# Main.net
KiCad netlist of a schematic drawn in Altium Designer
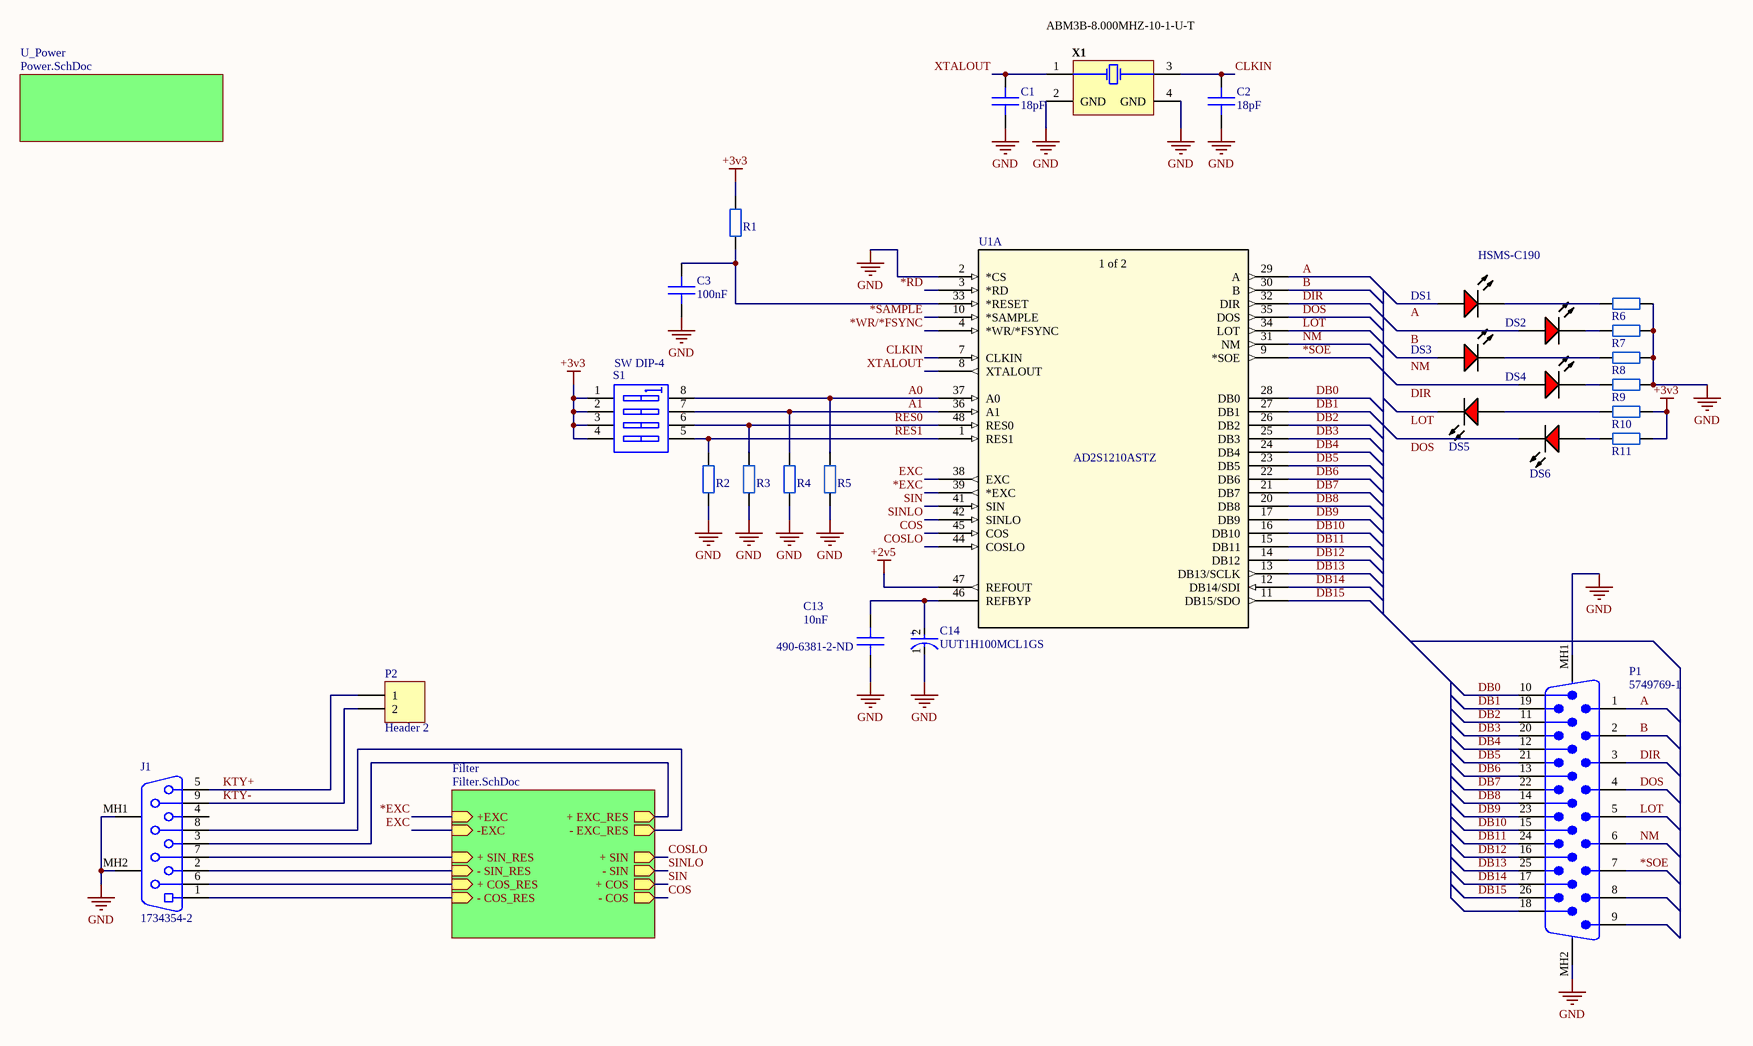
[diagram p0: Main.SchDoc]

(export (version "E")
  (design (tool "Eeschema 10.0.6"))
  (components
    (comp (ref "C1")
      (value "18pF")
      (footprint "C0603 (1608)")
      (fields (field (name "Comment") "Cap SMD"))
      (libsource (lib "Moto Symbol Lib") (part "Cap SMD"))
    )
    (comp (ref "C2")
      (value "18pF")
      (footprint "C0603 (1608)")
      (fields (field (name "Comment") "Cap SMD"))
      (libsource (lib "Moto Symbol Lib") (part "Cap SMD"))
    )
    (comp (ref "C3")
      (value "100nF")
      (footprint "C0603 (1608)")
      (fields (field (name "Comment") "Cap SMD"))
      (libsource (lib "Moto Symbol Lib") (part "Cap SMD"))
    )
    (comp (ref "C13")
      (value "10nF")
      (footprint "C0603 (1608)")
      (description "Multilayer Ceramic Capacitors MLCC - SMD/SMT 2200pF 50Volts 2%")
      (fields
        (field (name "SUPPLIER PART NUMBER 1") "490-6381-2-ND")
        (field (name "MANUFACTURER") "Murata")
        (field (name "MANUFACTURER PART NUMBER") "GRM1885C1H222GA01D")
      )
      (libsource (lib "Moto Symbol Lib") (part "Cap SMD"))
    )
    (comp (ref "C14")
      (value "UUT1H100MCL1GS")
      (footprint "FP-UUT1H100MCL1GS-MFG")
      (description "CAP ALUM 10UF 20% 50V SMD")
      (fields (field (name "VOLTAGE") "50V") (field (name "TOLERANCE") "20%"))
      (libsource (lib "Altium Content Vault") (part "cf48714ba7e38822c1575c7ec0b6d1f"))
    )
    (comp (ref "DS1")
      (value "HSMS-C190")
      (footprint "AVAG-HSMX-C190_V")
      (description "LED Uni-Color Red, 52 mW, 20 mA, -40 to 85 degC, 2-Pin SMD, RoHS, Tape and Reel")
      (fields (field (name "MANUFACTURER") "Avago"))
      (libsource (lib "Altium Content Vault") (part "LED-RED-AK-2"))
    )
    (comp (ref "DS2")
      (value "HSMS-C190")
      (footprint "AVAG-HSMX-C190_V")
      (description "LED Uni-Color Red, 52 mW, 20 mA, -40 to 85 degC, 2-Pin SMD, RoHS, Tape and Reel")
      (fields (field (name "MANUFACTURER") "Avago"))
      (libsource (lib "Altium Content Vault") (part "LED-RED-AK-2"))
    )
    (comp (ref "DS3")
      (value "HSMS-C190")
      (footprint "AVAG-HSMX-C190_V")
      (description "LED Uni-Color Red, 52 mW, 20 mA, -40 to 85 degC, 2-Pin SMD, RoHS, Tape and Reel")
      (fields (field (name "MANUFACTURER") "Avago"))
      (libsource (lib "Altium Content Vault") (part "LED-RED-AK-2"))
    )
    (comp (ref "DS4")
      (value "HSMS-C190")
      (footprint "AVAG-HSMX-C190_V")
      (description "LED Uni-Color Red, 52 mW, 20 mA, -40 to 85 degC, 2-Pin SMD, RoHS, Tape and Reel")
      (fields (field (name "MANUFACTURER") "Avago"))
      (libsource (lib "Altium Content Vault") (part "LED-RED-AK-2"))
    )
    (comp (ref "DS5")
      (value "HSMS-C190")
      (footprint "AVAG-HSMX-C190_V")
      (description "LED Uni-Color Red, 52 mW, 20 mA, -40 to 85 degC, 2-Pin SMD, RoHS, Tape and Reel")
      (fields (field (name "MANUFACTURER") "Avago"))
      (libsource (lib "Altium Content Vault") (part "LED-RED-AK-2"))
    )
    (comp (ref "DS6")
      (value "HSMS-C190")
      (footprint "AVAG-HSMX-C190_V")
      (description "LED Uni-Color Red, 52 mW, 20 mA, -40 to 85 degC, 2-Pin SMD, RoHS, Tape and Reel")
      (fields (field (name "MANUFACTURER") "Avago"))
      (libsource (lib "Altium Content Vault") (part "LED-RED-AK-2"))
    )
    (comp (ref "J1")
      (value "1734354-2")
      (footprint "TECO-1734354-2_V")
      (fields (field (name "MANUFACTURER") "TE Connectivity"))
      (libsource (lib "Altium Content Vault") (part "CN-2S-2F-D9"))
    )
    (comp (ref "P1")
      (value "5749769-1")
      (footprint "TECO-5749769-1_V")
      (fields (field (name "MANUFACTURER") "TEConnectivity"))
      (libsource (lib "Altium Content Vault") (part "CN-3S-2M-D26"))
    )
    (comp (ref "P2")
      (value "Header 2")
      (footprint "HDR1X2")
      (description "Header, 2-Pin")
      (fields (field (name "PUBLISHER") "Altium Limited"))
      (libsource (lib "Miscellaneous Connectors") (part "Header 2"))
    )
    (comp (ref "R1")
      (value "Res")
      (footprint "R0603 (1608)")
      (libsource (lib "Moto Symbol Lib") (part "Resistor EU"))
    )
    (comp (ref "R2")
      (value "Res")
      (footprint "R0603 (1608)")
      (libsource (lib "Moto Symbol Lib") (part "Resistor EU"))
    )
    (comp (ref "R3")
      (value "Res")
      (footprint "R0603 (1608)")
      (libsource (lib "Moto Symbol Lib") (part "Resistor EU"))
    )
    (comp (ref "R4")
      (value "Res")
      (footprint "R0603 (1608)")
      (libsource (lib "Moto Symbol Lib") (part "Resistor EU"))
    )
    (comp (ref "R5")
      (value "Res")
      (footprint "R0603 (1608)")
      (libsource (lib "Moto Symbol Lib") (part "Resistor EU"))
    )
    (comp (ref "R6")
      (value "1K")
      (footprint "R0603 (1608)")
      (libsource (lib "Moto Symbol Lib") (part "Resistor EU"))
    )
    (comp (ref "R7")
      (value "1K")
      (footprint "R0603 (1608)")
      (libsource (lib "Moto Symbol Lib") (part "Resistor EU"))
    )
    (comp (ref "R8")
      (value "1K")
      (footprint "R0603 (1608)")
      (libsource (lib "Moto Symbol Lib") (part "Resistor EU"))
    )
    (comp (ref "R9")
      (value "1K")
      (footprint "R0603 (1608)")
      (libsource (lib "Moto Symbol Lib") (part "Resistor EU"))
    )
    (comp (ref "R10")
      (value "1K")
      (footprint "R0603 (1608)")
      (libsource (lib "Moto Symbol Lib") (part "Resistor EU"))
    )
    (comp (ref "R11")
      (value "1K")
      (footprint "R0603 (1608)")
      (libsource (lib "Moto Symbol Lib") (part "Resistor EU"))
    )
    (comp (ref "S1")
      (value "SW DIP-4")
      (footprint "SO8_M")
      (description "DIP Switch, 4 Position, SPST")
      (fields (field (name "PUBLISHER") "Altium Limited"))
      (libsource (lib "Miscellaneous Devices") (part "SW DIP-4"))
    )
    (comp (ref "U1")
      (value "AD2S1210ASTZ")
      (footprint "ST_48_ADI")
      (description "No Description Available")
      (fields (field (name "COPYRIGHT") "Copyright (C) 2018 Accelerated Designs. All rights reserved"))
      (libsource (lib "Resolver Lib") (part "AD2S1210ASTZ"))
    )
    (comp (ref "X1")
      (value "ABM3B-8.000MHZ-10-1-U-T")
      (footprint "ABRA-ABM3B_V")
      (description "Ceramic Crystal, 8 MHz, +/- 10 ppm, -10 to 60 degC, 4-Pin SMD, RoHS, Tape and Reel")
      (fields (field (name "MANUFACTURER") "Abracon-LLC"))
      (libsource (lib "Altium Content Vault") (part "XTAL-1-3-4"))
    )
  )
  (nets
    (net (code "1") (name "+2v5") (class "Default")
      (node (ref "U1") (pin "47") (pinfunction "REFOUT_47") (pintype "output"))
    )
    (net (code "2") (name "+3v3") (class "Default")
      (node (ref "R1") (pin "2") (pinfunction "2_2") (pintype "power_in"))
      (node (ref "R10") (pin "2") (pinfunction "2_2") (pintype "power_in"))
      (node (ref "R11") (pin "2") (pinfunction "2_2") (pintype "power_in"))
      (node (ref "S1") (pin "1") (pinfunction "A1_1") (pintype "passive"))
      (node (ref "S1") (pin "2") (pinfunction "A2_2") (pintype "passive"))
      (node (ref "S1") (pin "3") (pinfunction "A3_3") (pintype "passive"))
      (node (ref "S1") (pin "4") (pinfunction "A4_4") (pintype "passive"))
    )
    (net (code "3") (name "/*EXC") (class "Default")
      (node (ref "U1") (pin "39") (pinfunction "*EXC_39") (pintype "output"))
    )
    (net (code "4") (name "/*RD") (class "Default")
      (node (ref "U1") (pin "3") (pinfunction "*RD_3") (pintype "input"))
    )
    (net (code "5") (name "/*SAMPLE") (class "Default")
      (node (ref "U1") (pin "10") (pinfunction "*SAMPLE_10") (pintype "input"))
    )
    (net (code "6") (name "/*SOE") (class "Default")
      (node (ref "P1") (pin "7") (pinfunction "7_7") (pintype "passive"))
      (node (ref "U1") (pin "9") (pinfunction "*SOE_9") (pintype "output"))
    )
    (net (code "7") (name "/*WR{slash}*FSYNC") (class "Default")
      (node (ref "U1") (pin "4") (pinfunction "*WR/*FSYNC_4") (pintype "input"))
    )
    (net (code "8") (name "/+ COS_RES") (class "Default")
      (node (ref "J1") (pin "6") (pinfunction "6_6") (pintype "passive"))
    )
    (net (code "9") (name "/+ EXC_RES") (class "Default")
      (node (ref "J1") (pin "3") (pinfunction "3_3") (pintype "passive"))
    )
    (net (code "10") (name "/+ SIN_RES") (class "Default")
      (node (ref "J1") (pin "7") (pinfunction "7_7") (pintype "passive"))
    )
    (net (code "11") (name "/- COS_RES") (class "Default")
      (node (ref "J1") (pin "1") (pinfunction "1_1") (pintype "passive"))
    )
    (net (code "12") (name "/- EXC_RES") (class "Default")
      (node (ref "J1") (pin "8") (pinfunction "8_8") (pintype "passive"))
    )
    (net (code "13") (name "/- SIN_RES") (class "Default")
      (node (ref "J1") (pin "2") (pinfunction "2_2") (pintype "passive"))
    )
    (net (code "14") (name "/A") (class "Default")
      (node (ref "DS1") (pin "1") (pinfunction "A_1") (pintype "passive"))
      (node (ref "P1") (pin "1") (pinfunction "1_1") (pintype "passive"))
      (node (ref "U1") (pin "29") (pinfunction "A_29") (pintype "output"))
    )
    (net (code "15") (name "/A0") (class "Default")
      (node (ref "R5") (pin "2") (pinfunction "2_2") (pintype "power_in"))
      (node (ref "S1") (pin "8") (pinfunction "B1_8") (pintype "passive"))
      (node (ref "U1") (pin "37") (pinfunction "A0_37") (pintype "input"))
    )
    (net (code "16") (name "/A1") (class "Default")
      (node (ref "R4") (pin "2") (pinfunction "2_2") (pintype "power_in"))
      (node (ref "S1") (pin "7") (pinfunction "B2_7") (pintype "passive"))
      (node (ref "U1") (pin "36") (pinfunction "A1_36") (pintype "input"))
    )
    (net (code "17") (name "/B") (class "Default")
      (node (ref "DS2") (pin "1") (pinfunction "A_1") (pintype "passive"))
      (node (ref "P1") (pin "2") (pinfunction "2_2") (pintype "passive"))
      (node (ref "U1") (pin "30") (pinfunction "B_30") (pintype "output"))
    )
    (net (code "18") (name "/CLKIN") (class "Default")
      (node (ref "C2") (pin "2") (pinfunction "2_2") (pintype "power_in"))
      (node (ref "U1") (pin "7") (pinfunction "CLKIN_7") (pintype "input"))
      (node (ref "X1") (pin "3") (pinfunction "X2_3") (pintype "passive"))
    )
    (net (code "19") (name "/COS") (class "Default")
      (node (ref "U1") (pin "45") (pinfunction "COS_45") (pintype "input"))
    )
    (net (code "20") (name "/COSLO") (class "Default")
      (node (ref "U1") (pin "44") (pinfunction "COSLO_44") (pintype "input"))
    )
    (net (code "21") (name "/DB0") (class "Default")
      (node (ref "P1") (pin "10") (pinfunction "10_10") (pintype "passive"))
      (node (ref "U1") (pin "28") (pinfunction "DB0_28") (pintype "passive"))
    )
    (net (code "22") (name "/DB1") (class "Default")
      (node (ref "P1") (pin "19") (pinfunction "19_19") (pintype "passive"))
      (node (ref "U1") (pin "27") (pinfunction "DB1_27") (pintype "passive"))
    )
    (net (code "23") (name "/DB2") (class "Default")
      (node (ref "P1") (pin "11") (pinfunction "11_11") (pintype "passive"))
      (node (ref "U1") (pin "26") (pinfunction "DB2_26") (pintype "passive"))
    )
    (net (code "24") (name "/DB3") (class "Default")
      (node (ref "P1") (pin "20") (pinfunction "20_20") (pintype "passive"))
      (node (ref "U1") (pin "25") (pinfunction "DB3_25") (pintype "passive"))
    )
    (net (code "25") (name "/DB4") (class "Default")
      (node (ref "P1") (pin "12") (pinfunction "12_12") (pintype "passive"))
      (node (ref "U1") (pin "24") (pinfunction "DB4_24") (pintype "passive"))
    )
    (net (code "26") (name "/DB5") (class "Default")
      (node (ref "P1") (pin "21") (pinfunction "21_21") (pintype "passive"))
      (node (ref "U1") (pin "23") (pinfunction "DB5_23") (pintype "passive"))
    )
    (net (code "27") (name "/DB6") (class "Default")
      (node (ref "P1") (pin "13") (pinfunction "13_13") (pintype "passive"))
      (node (ref "U1") (pin "22") (pinfunction "DB6_22") (pintype "passive"))
    )
    (net (code "28") (name "/DB7") (class "Default")
      (node (ref "P1") (pin "22") (pinfunction "22_22") (pintype "passive"))
      (node (ref "U1") (pin "21") (pinfunction "DB7_21") (pintype "passive"))
    )
    (net (code "29") (name "/DB8") (class "Default")
      (node (ref "P1") (pin "14") (pinfunction "14_14") (pintype "passive"))
      (node (ref "U1") (pin "20") (pinfunction "DB8_20") (pintype "passive"))
    )
    (net (code "30") (name "/DB9") (class "Default")
      (node (ref "P1") (pin "23") (pinfunction "23_23") (pintype "passive"))
      (node (ref "U1") (pin "17") (pinfunction "DB9_17") (pintype "passive"))
    )
    (net (code "31") (name "/DB10") (class "Default")
      (node (ref "P1") (pin "15") (pinfunction "15_15") (pintype "passive"))
      (node (ref "U1") (pin "16") (pinfunction "DB10_16") (pintype "passive"))
    )
    (net (code "32") (name "/DB11") (class "Default")
      (node (ref "P1") (pin "24") (pinfunction "24_24") (pintype "passive"))
      (node (ref "U1") (pin "15") (pinfunction "DB11_15") (pintype "passive"))
    )
    (net (code "33") (name "/DB12") (class "Default")
      (node (ref "P1") (pin "16") (pinfunction "16_16") (pintype "passive"))
      (node (ref "U1") (pin "14") (pinfunction "DB12_14") (pintype "passive"))
    )
    (net (code "34") (name "/DB13") (class "Default")
      (node (ref "P1") (pin "25") (pinfunction "25_25") (pintype "passive"))
      (node (ref "U1") (pin "13") (pinfunction "DB13/SCLK_13") (pintype "output"))
    )
    (net (code "35") (name "/DB14") (class "Default")
      (node (ref "P1") (pin "17") (pinfunction "17_17") (pintype "passive"))
      (node (ref "U1") (pin "12") (pinfunction "DB14/SDI_12") (pintype "input"))
    )
    (net (code "36") (name "/DB15") (class "Default")
      (node (ref "P1") (pin "26") (pinfunction "26_26") (pintype "passive"))
      (node (ref "U1") (pin "11") (pinfunction "DB15/SDO_11") (pintype "output"))
    )
    (net (code "37") (name "/DIR") (class "Default")
      (node (ref "DS4") (pin "1") (pinfunction "A_1") (pintype "passive"))
      (node (ref "P1") (pin "3") (pinfunction "3_3") (pintype "passive"))
      (node (ref "U1") (pin "32") (pinfunction "DIR_32") (pintype "output"))
    )
    (net (code "38") (name "/DOS") (class "Default")
      (node (ref "DS6") (pin "2") (pinfunction "K_2") (pintype "passive"))
      (node (ref "P1") (pin "4") (pinfunction "4_4") (pintype "passive"))
      (node (ref "U1") (pin "35") (pinfunction "DOS_35") (pintype "output"))
    )
    (net (code "39") (name "/EXC") (class "Default")
      (node (ref "U1") (pin "38") (pinfunction "EXC_38") (pintype "output"))
    )
    (net (code "40") (name "/KTY+") (class "Default")
      (node (ref "J1") (pin "5") (pinfunction "5_5") (pintype "passive"))
      (node (ref "P2") (pin "1") (pinfunction "1_1") (pintype "passive"))
    )
    (net (code "41") (name "/KTY-") (class "Default")
      (node (ref "J1") (pin "9") (pinfunction "9_9") (pintype "passive"))
      (node (ref "P2") (pin "2") (pinfunction "2_2") (pintype "passive"))
    )
    (net (code "42") (name "/LOT") (class "Default")
      (node (ref "DS5") (pin "2") (pinfunction "K_2") (pintype "passive"))
      (node (ref "P1") (pin "5") (pinfunction "5_5") (pintype "passive"))
      (node (ref "U1") (pin "34") (pinfunction "LOT_34") (pintype "output"))
    )
    (net (code "43") (name "/NM") (class "Default")
      (node (ref "DS3") (pin "1") (pinfunction "A_1") (pintype "passive"))
      (node (ref "P1") (pin "6") (pinfunction "6_6") (pintype "passive"))
      (node (ref "U1") (pin "31") (pinfunction "NM_31") (pintype "output"))
    )
    (net (code "44") (name "/RES0") (class "Default")
      (node (ref "R3") (pin "2") (pinfunction "2_2") (pintype "power_in"))
      (node (ref "S1") (pin "6") (pinfunction "B3_6") (pintype "passive"))
      (node (ref "U1") (pin "48") (pinfunction "RES0_48") (pintype "input"))
    )
    (net (code "45") (name "/RES1") (class "Default")
      (node (ref "R2") (pin "2") (pinfunction "2_2") (pintype "power_in"))
      (node (ref "S1") (pin "5") (pinfunction "B4_5") (pintype "passive"))
      (node (ref "U1") (pin "1") (pinfunction "RES1_1") (pintype "input"))
    )
    (net (code "46") (name "/SIN") (class "Default")
      (node (ref "U1") (pin "41") (pinfunction "SIN_41") (pintype "input"))
    )
    (net (code "47") (name "/SINLO") (class "Default")
      (node (ref "U1") (pin "42") (pinfunction "SINLO_42") (pintype "input"))
    )
    (net (code "48") (name "/XTALOUT") (class "Default")
      (node (ref "C1") (pin "2") (pinfunction "2_2") (pintype "power_in"))
      (node (ref "U1") (pin "8") (pinfunction "XTALOUT_8") (pintype "output"))
      (node (ref "X1") (pin "1") (pinfunction "X1_1") (pintype "passive"))
    )
    (net (code "49") (name "GND") (class "Default")
      (node (ref "C1") (pin "1") (pinfunction "1_1") (pintype "power_in"))
      (node (ref "C13") (pin "1") (pinfunction "1_1") (pintype "power_in"))
      (node (ref "C14") (pin "1") (pinfunction "C_1") (pintype "passive"))
      (node (ref "C2") (pin "1") (pinfunction "1_1") (pintype "power_in"))
      (node (ref "C3") (pin "1") (pinfunction "1_1") (pintype "power_in"))
      (node (ref "J1") (pin "MH1") (pinfunction "MH1_MH1") (pintype "passive"))
      (node (ref "J1") (pin "MH2") (pinfunction "MH2_MH2") (pintype "passive"))
      (node (ref "P1") (pin "MH1") (pinfunction "MH1_MH1") (pintype "passive"))
      (node (ref "P1") (pin "MH2") (pinfunction "MH2_MH2") (pintype "passive"))
      (node (ref "R2") (pin "1") (pinfunction "1_1") (pintype "power_in"))
      (node (ref "R3") (pin "1") (pinfunction "1_1") (pintype "power_in"))
      (node (ref "R4") (pin "1") (pinfunction "1_1") (pintype "power_in"))
      (node (ref "R5") (pin "1") (pinfunction "1_1") (pintype "power_in"))
      (node (ref "R6") (pin "2") (pinfunction "2_2") (pintype "power_in"))
      (node (ref "R7") (pin "2") (pinfunction "2_2") (pintype "power_in"))
      (node (ref "R8") (pin "2") (pinfunction "2_2") (pintype "power_in"))
      (node (ref "R9") (pin "2") (pinfunction "2_2") (pintype "power_in"))
      (node (ref "U1") (pin "2") (pinfunction "*CS_2") (pintype "input"))
      (node (ref "X1") (pin "2") (pinfunction "GND_2") (pintype "power_in"))
      (node (ref "X1") (pin "4") (pinfunction "GND_4") (pintype "power_in"))
    )
    (net (code "50") (name "Net-(C14-A)") (class "Default")
      (node (ref "C13") (pin "2") (pinfunction "2_2") (pintype "power_in"))
      (node (ref "C14") (pin "2") (pinfunction "A_2") (pintype "passive"))
      (node (ref "U1") (pin "46") (pinfunction "REFBYP_46") (pintype "passive"))
    )
    (net (code "51") (name "Net-(DS1-K)") (class "Default")
      (node (ref "DS1") (pin "2") (pinfunction "K_2") (pintype "passive"))
      (node (ref "R6") (pin "1") (pinfunction "1_1") (pintype "power_in"))
    )
    (net (code "52") (name "Net-(DS2-K)") (class "Default")
      (node (ref "DS2") (pin "2") (pinfunction "K_2") (pintype "passive"))
      (node (ref "R7") (pin "1") (pinfunction "1_1") (pintype "power_in"))
    )
    (net (code "53") (name "Net-(DS3-K)") (class "Default")
      (node (ref "DS3") (pin "2") (pinfunction "K_2") (pintype "passive"))
      (node (ref "R8") (pin "1") (pinfunction "1_1") (pintype "power_in"))
    )
    (net (code "54") (name "Net-(DS4-K)") (class "Default")
      (node (ref "DS4") (pin "2") (pinfunction "K_2") (pintype "passive"))
      (node (ref "R9") (pin "1") (pinfunction "1_1") (pintype "power_in"))
    )
    (net (code "55") (name "Net-(DS5-A)") (class "Default")
      (node (ref "DS5") (pin "1") (pinfunction "A_1") (pintype "passive"))
      (node (ref "R10") (pin "1") (pinfunction "1_1") (pintype "power_in"))
    )
    (net (code "56") (name "Net-(DS6-A)") (class "Default")
      (node (ref "DS6") (pin "1") (pinfunction "A_1") (pintype "passive"))
      (node (ref "R11") (pin "1") (pinfunction "1_1") (pintype "power_in"))
    )
    (net (code "57") (name "Net-(U1A-*RESET)") (class "Default")
      (node (ref "C3") (pin "2") (pinfunction "2_2") (pintype "power_in"))
      (node (ref "R1") (pin "1") (pinfunction "1_1") (pintype "power_in"))
      (node (ref "U1") (pin "33") (pinfunction "*RESET_33") (pintype "input"))
    )
    (net (code "58") (name "unconnected-(J1-Pad4)") (class "Default")
      (node (ref "J1") (pin "4") (pinfunction "4_4") (pintype "passive"))
    )
    (net (code "59") (name "unconnected-(P1-Pad8)") (class "Default")
      (node (ref "P1") (pin "8") (pinfunction "8_8") (pintype "passive"))
    )
    (net (code "60") (name "unconnected-(P1-Pad9)") (class "Default")
      (node (ref "P1") (pin "9") (pinfunction "9_9") (pintype "passive"))
    )
    (net (code "61") (name "unconnected-(P1-Pad18)") (class "Default")
      (node (ref "P1") (pin "18") (pinfunction "18_18") (pintype "passive"))
    )
  )
)
